# Ikaruga.net
KiCad netlist of a schematic drawn in EAGLE
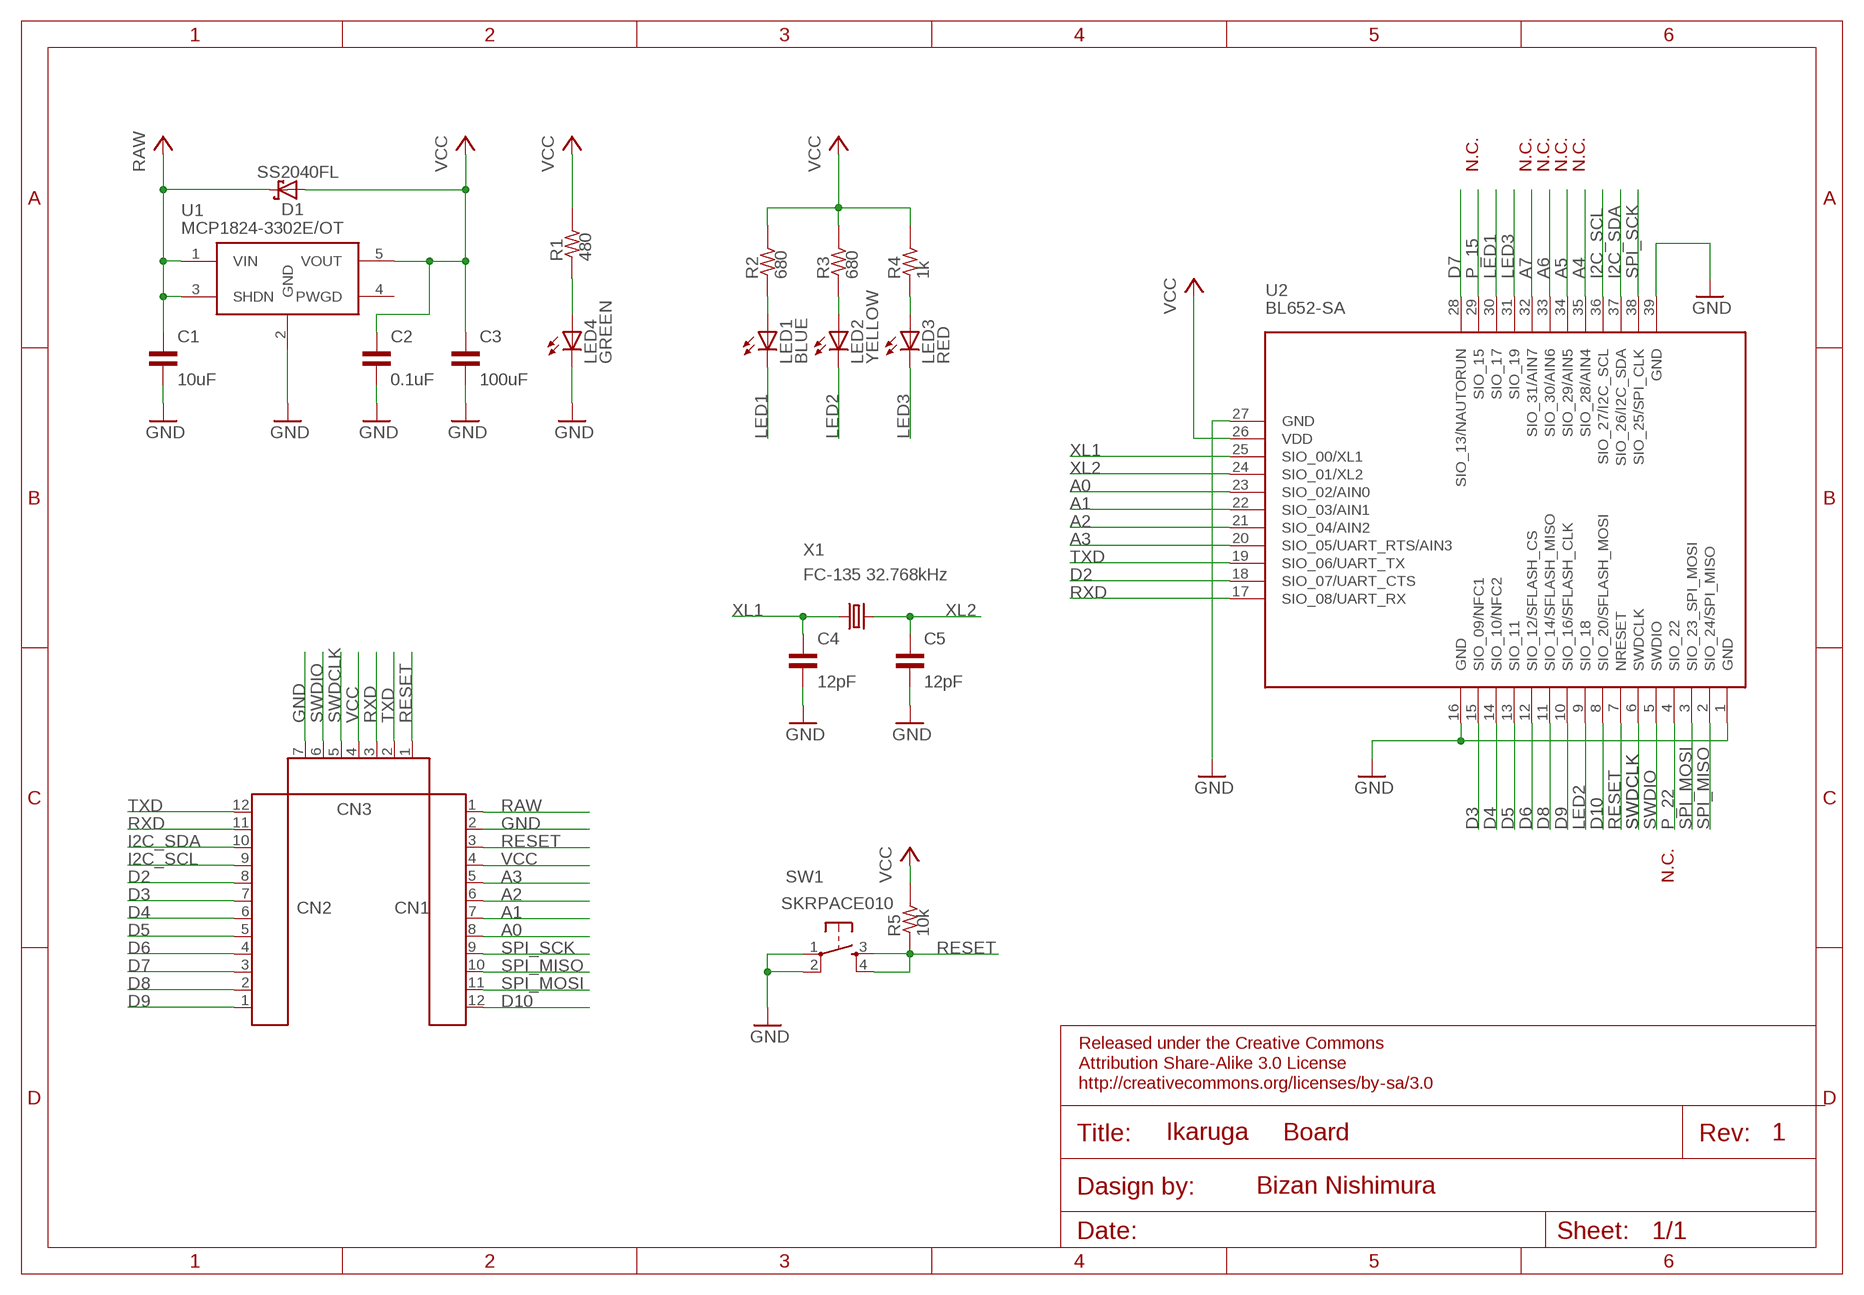
[diagram p0: schematic, sheet 1]

(export (version "E")
  (design (tool "Eeschema 10.0.6"))
  (components
    (comp (ref "C1")
      (value "10uF")
      (footprint "eagle-import:CP3216")
      (libsource (lib "eagle-import") (part "C-CP-3216"))
    )
    (comp (ref "C2")
      (value "0.1uF")
      (footprint "eagle-import:CP1608")
      (libsource (lib "eagle-import") (part "C-CP-1608"))
    )
    (comp (ref "C3")
      (value "100uF")
      (footprint "eagle-import:CP3216")
      (libsource (lib "eagle-import") (part "C-CP-3216"))
    )
    (comp (ref "C4")
      (value "12pF")
      (footprint "eagle-import:CP1608")
      (libsource (lib "eagle-import") (part "C-CP-1608"))
    )
    (comp (ref "C5")
      (value "12pF")
      (footprint "eagle-import:CP1608")
      (libsource (lib "eagle-import") (part "C-CP-1608"))
    )
    (comp (ref "CN1")
      (value "PINHD-1X12-NO-LINE")
      (footprint "eagle-import:1X12-NO-LINE")
      (libsource (lib "eagle-import") (part "PINHD-1X12-NO-LINE"))
    )
    (comp (ref "CN2")
      (value "PINHD-1X12-NO-LINE")
      (footprint "eagle-import:1X12-NO-LINE")
      (libsource (lib "eagle-import") (part "PINHD-1X12-NO-LINE"))
    )
    (comp (ref "CN3")
      (value "PINHD-1X7-NO-LINE")
      (footprint "eagle-import:1X07-NO-LINE")
      (libsource (lib "eagle-import") (part "PINHD-1X7-NO-LINE"))
    )
    (comp (ref "D1")
      (value "SS2040FL")
      (footprint "eagle-import:SOD123")
      (libsource (lib "eagle-import") (part "SCHOTTKY-DIODE-SOD123"))
    )
    (comp (ref "LED1")
      (value "BLUE")
      (footprint "eagle-import:LED1608")
      (libsource (lib "eagle-import") (part "LED1608"))
    )
    (comp (ref "LED2")
      (value "YELLOW")
      (footprint "eagle-import:LED1608")
      (libsource (lib "eagle-import") (part "LED1608"))
    )
    (comp (ref "LED3")
      (value "RED")
      (footprint "eagle-import:LED1608")
      (libsource (lib "eagle-import") (part "LED1608"))
    )
    (comp (ref "LED4")
      (value "GREEN")
      (footprint "eagle-import:LED1608")
      (libsource (lib "eagle-import") (part "LED1608"))
    )
    (comp (ref "R1")
      (value "480")
      (footprint "eagle-import:CP1608")
      (libsource (lib "eagle-import") (part "R-CP-1608"))
    )
    (comp (ref "R2")
      (value "680")
      (footprint "eagle-import:CP1608")
      (libsource (lib "eagle-import") (part "R-CP-1608"))
    )
    (comp (ref "R3")
      (value "680")
      (footprint "eagle-import:CP1608")
      (libsource (lib "eagle-import") (part "R-CP-1608"))
    )
    (comp (ref "R4")
      (value "1k")
      (footprint "eagle-import:CP1608")
      (libsource (lib "eagle-import") (part "R-CP-1608"))
    )
    (comp (ref "R5")
      (value "10k")
      (footprint "eagle-import:CP1608")
      (libsource (lib "eagle-import") (part "R-CP-1608"))
    )
    (comp (ref "SW1")
      (value "SKRPACE010")
      (footprint "eagle-import:SKRPACE010")
      (libsource (lib "eagle-import") (part "SKRPACE010"))
    )
    (comp (ref "U1")
      (value "MCP1824-3302E/OT")
      (footprint "eagle-import:SOT-23-5")
      (libsource (lib "eagle-import") (part "MCP1824-3302E/OT"))
    )
    (comp (ref "U2")
      (value "BL652-SA")
      (footprint "eagle-import:BL652-SA")
      (libsource (lib "eagle-import") (part "BL652-SA"))
    )
    (comp (ref "X1")
      (value "FC-135 32.768kHz")
      (footprint "eagle-import:FC-135")
      (libsource (lib "eagle-import") (part "FC-135"))
    )
  )
  (nets
    (net (code "1") (name "/A0") (class "Default")
      (node (ref "CN1") (pin "8") (pinfunction "8_8") (pintype "bidirectional"))
      (node (ref "U2") (pin "23") (pinfunction "SIO_02/AIN0_23") (pintype "bidirectional"))
    )
    (net (code "2") (name "/A1") (class "Default")
      (node (ref "CN1") (pin "7") (pinfunction "7_7") (pintype "bidirectional"))
      (node (ref "U2") (pin "22") (pinfunction "SIO_03/AIN1_22") (pintype "bidirectional"))
    )
    (net (code "3") (name "/A2") (class "Default")
      (node (ref "CN1") (pin "6") (pinfunction "6_6") (pintype "bidirectional"))
      (node (ref "U2") (pin "21") (pinfunction "SIO_04/AIN2_21") (pintype "bidirectional"))
    )
    (net (code "4") (name "/A3") (class "Default")
      (node (ref "CN1") (pin "5") (pinfunction "5_5") (pintype "bidirectional"))
      (node (ref "U2") (pin "20") (pinfunction "SIO_05/UART_RTS/AIN3_20") (pintype "bidirectional"))
    )
    (net (code "5") (name "/A4") (class "Default")
      (node (ref "U2") (pin "35") (pinfunction "SIO_28/AIN4_35") (pintype "bidirectional"))
    )
    (net (code "6") (name "/A5") (class "Default")
      (node (ref "U2") (pin "34") (pinfunction "SIO_29/AIN5_34") (pintype "bidirectional"))
    )
    (net (code "7") (name "/A6") (class "Default")
      (node (ref "U2") (pin "33") (pinfunction "SIO_30/AIN6_33") (pintype "bidirectional"))
    )
    (net (code "8") (name "/A7") (class "Default")
      (node (ref "U2") (pin "32") (pinfunction "SIO_31/AIN7_32") (pintype "bidirectional"))
    )
    (net (code "9") (name "/D2") (class "Default")
      (node (ref "CN2") (pin "8") (pinfunction "8_8") (pintype "bidirectional"))
      (node (ref "U2") (pin "18") (pinfunction "SIO_07/UART_CTS_18") (pintype "bidirectional"))
    )
    (net (code "10") (name "/D3") (class "Default")
      (node (ref "CN2") (pin "7") (pinfunction "7_7") (pintype "bidirectional"))
      (node (ref "U2") (pin "15") (pinfunction "SIO_09/NFC1_15") (pintype "bidirectional"))
    )
    (net (code "11") (name "/D4") (class "Default")
      (node (ref "CN2") (pin "6") (pinfunction "6_6") (pintype "bidirectional"))
      (node (ref "U2") (pin "14") (pinfunction "SIO_10/NFC2_14") (pintype "bidirectional"))
    )
    (net (code "12") (name "/D5") (class "Default")
      (node (ref "CN2") (pin "5") (pinfunction "5_5") (pintype "bidirectional"))
      (node (ref "U2") (pin "13") (pinfunction "SIO_11_13") (pintype "bidirectional"))
    )
    (net (code "13") (name "/D6") (class "Default")
      (node (ref "CN2") (pin "4") (pinfunction "4_4") (pintype "bidirectional"))
      (node (ref "U2") (pin "12") (pinfunction "SIO_12/SFLASH_CS_12") (pintype "bidirectional"))
    )
    (net (code "14") (name "/D7") (class "Default")
      (node (ref "CN2") (pin "3") (pinfunction "3_3") (pintype "bidirectional"))
      (node (ref "U2") (pin "28") (pinfunction "SIO_13/NAUTORUN_28") (pintype "bidirectional"))
    )
    (net (code "15") (name "/D8") (class "Default")
      (node (ref "CN2") (pin "2") (pinfunction "2_2") (pintype "bidirectional"))
      (node (ref "U2") (pin "11") (pinfunction "SIO_14/SFLASH_MISO_11") (pintype "bidirectional"))
    )
    (net (code "16") (name "/D9") (class "Default")
      (node (ref "CN2") (pin "1") (pinfunction "1_1") (pintype "bidirectional"))
      (node (ref "U2") (pin "10") (pinfunction "SIO_16/SFLASH_CLK_10") (pintype "bidirectional"))
    )
    (net (code "17") (name "/D10") (class "Default")
      (node (ref "CN1") (pin "12") (pinfunction "12_12") (pintype "bidirectional"))
      (node (ref "U2") (pin "8") (pinfunction "SIO_20/SFLASH_MOSI_8") (pintype "bidirectional"))
    )
    (net (code "18") (name "/I2C_SCL") (class "Default")
      (node (ref "CN2") (pin "9") (pinfunction "9_9") (pintype "bidirectional"))
      (node (ref "U2") (pin "36") (pinfunction "SIO_27/I2C_SCL_36") (pintype "bidirectional"))
    )
    (net (code "19") (name "/I2C_SDA") (class "Default")
      (node (ref "CN2") (pin "10") (pinfunction "10_10") (pintype "bidirectional"))
      (node (ref "U2") (pin "37") (pinfunction "SIO_26/I2C_SDA_37") (pintype "bidirectional"))
    )
    (net (code "20") (name "/LED1") (class "Default")
      (node (ref "LED1") (pin "C") (pinfunction "C_C") (pintype "passive"))
      (node (ref "U2") (pin "30") (pinfunction "SIO_17_30") (pintype "bidirectional"))
    )
    (net (code "21") (name "/LED2") (class "Default")
      (node (ref "LED2") (pin "C") (pinfunction "C_C") (pintype "passive"))
      (node (ref "U2") (pin "9") (pinfunction "SIO_18_9") (pintype "bidirectional"))
    )
    (net (code "22") (name "/LED3") (class "Default")
      (node (ref "LED3") (pin "C") (pinfunction "C_C") (pintype "passive"))
      (node (ref "U2") (pin "31") (pinfunction "SIO_19_31") (pintype "bidirectional"))
    )
    (net (code "23") (name "/P_15") (class "Default")
      (node (ref "U2") (pin "29") (pinfunction "SIO_15_29") (pintype "bidirectional"))
    )
    (net (code "24") (name "/P_22") (class "Default")
      (node (ref "U2") (pin "4") (pinfunction "SIO_22_4") (pintype "bidirectional"))
    )
    (net (code "25") (name "/RESET") (class "Default")
      (node (ref "CN1") (pin "3") (pinfunction "3_3") (pintype "bidirectional"))
      (node (ref "CN3") (pin "1") (pinfunction "1_1") (pintype "bidirectional"))
      (node (ref "R5") (pin "SMD1") (pinfunction "PIN1_SMD1") (pintype "passive"))
      (node (ref "SW1") (pin "3") (pinfunction "3_3") (pintype "passive"))
      (node (ref "SW1") (pin "4") (pinfunction "4_4") (pintype "passive"))
      (node (ref "U2") (pin "7") (pinfunction "NRESET_7") (pintype "bidirectional"))
    )
    (net (code "26") (name "/RXD") (class "Default")
      (node (ref "CN2") (pin "11") (pinfunction "11_11") (pintype "bidirectional"))
      (node (ref "CN3") (pin "3") (pinfunction "3_3") (pintype "bidirectional"))
      (node (ref "U2") (pin "17") (pinfunction "SIO_08/UART_RX_17") (pintype "bidirectional"))
    )
    (net (code "27") (name "/SPI_MISO") (class "Default")
      (node (ref "CN1") (pin "10") (pinfunction "10_10") (pintype "bidirectional"))
      (node (ref "U2") (pin "2") (pinfunction "SIO_24/SPI_MISO_2") (pintype "bidirectional"))
    )
    (net (code "28") (name "/SPI_MOSI") (class "Default")
      (node (ref "CN1") (pin "11") (pinfunction "11_11") (pintype "bidirectional"))
      (node (ref "U2") (pin "3") (pinfunction "SIO_23_SPI_MOSI_3") (pintype "bidirectional"))
    )
    (net (code "29") (name "/SPI_SCK") (class "Default")
      (node (ref "CN1") (pin "9") (pinfunction "9_9") (pintype "bidirectional"))
      (node (ref "U2") (pin "38") (pinfunction "SIO_25/SPI_CLK_38") (pintype "bidirectional"))
    )
    (net (code "30") (name "/SWDCLK") (class "Default")
      (node (ref "CN3") (pin "5") (pinfunction "5_5") (pintype "bidirectional"))
      (node (ref "U2") (pin "6") (pinfunction "SWDCLK_6") (pintype "bidirectional"))
    )
    (net (code "31") (name "/SWDIO") (class "Default")
      (node (ref "CN3") (pin "6") (pinfunction "6_6") (pintype "bidirectional"))
      (node (ref "U2") (pin "5") (pinfunction "SWDIO_5") (pintype "bidirectional"))
    )
    (net (code "32") (name "/TXD") (class "Default")
      (node (ref "CN2") (pin "12") (pinfunction "12_12") (pintype "bidirectional"))
      (node (ref "CN3") (pin "2") (pinfunction "2_2") (pintype "bidirectional"))
      (node (ref "U2") (pin "19") (pinfunction "SIO_06/UART_TX_19") (pintype "bidirectional"))
    )
    (net (code "33") (name "/XL1") (class "Default")
      (node (ref "C4") (pin "SMD1") (pinfunction "PIN1_SMD1") (pintype "passive"))
      (node (ref "U2") (pin "25") (pinfunction "SIO_00/XL1_25") (pintype "bidirectional"))
      (node (ref "X1") (pin "1") (pinfunction "1_1") (pintype "passive"))
    )
    (net (code "34") (name "/XL2") (class "Default")
      (node (ref "C5") (pin "SMD1") (pinfunction "PIN1_SMD1") (pintype "passive"))
      (node (ref "U2") (pin "24") (pinfunction "SIO_01/XL2_24") (pintype "bidirectional"))
      (node (ref "X1") (pin "2") (pinfunction "2_2") (pintype "passive"))
    )
    (net (code "35") (name "GND") (class "Default")
      (node (ref "C1") (pin "SMD2") (pinfunction "PIN2_SMD2") (pintype "passive"))
      (node (ref "C2") (pin "SMD2") (pinfunction "PIN2_SMD2") (pintype "passive"))
      (node (ref "C3") (pin "SMD2") (pinfunction "PIN2_SMD2") (pintype "passive"))
      (node (ref "C4") (pin "SMD2") (pinfunction "PIN2_SMD2") (pintype "passive"))
      (node (ref "C5") (pin "SMD2") (pinfunction "PIN2_SMD2") (pintype "passive"))
      (node (ref "CN1") (pin "2") (pinfunction "2_2") (pintype "bidirectional"))
      (node (ref "CN3") (pin "7") (pinfunction "7_7") (pintype "bidirectional"))
      (node (ref "LED4") (pin "C") (pinfunction "C_C") (pintype "passive"))
      (node (ref "SW1") (pin "1") (pinfunction "1_1") (pintype "passive"))
      (node (ref "SW1") (pin "2") (pinfunction "2_2") (pintype "passive"))
      (node (ref "U1") (pin "2") (pinfunction "GND_2") (pintype "bidirectional"))
      (node (ref "U2") (pin "1") (pinfunction "GND_1") (pintype "bidirectional"))
      (node (ref "U2") (pin "16") (pinfunction "GND_16") (pintype "bidirectional"))
      (node (ref "U2") (pin "27") (pinfunction "GND_27") (pintype "bidirectional"))
      (node (ref "U2") (pin "39") (pinfunction "GND_39") (pintype "bidirectional"))
    )
    (net (code "36") (name "Net-(R1-PIN1)") (class "Default")
      (node (ref "LED4") (pin "A") (pinfunction "A_A") (pintype "passive"))
      (node (ref "R1") (pin "SMD1") (pinfunction "PIN1_SMD1") (pintype "passive"))
    )
    (net (code "37") (name "Net-(R2-PIN1)") (class "Default")
      (node (ref "LED1") (pin "A") (pinfunction "A_A") (pintype "passive"))
      (node (ref "R2") (pin "SMD1") (pinfunction "PIN1_SMD1") (pintype "passive"))
    )
    (net (code "38") (name "Net-(R3-PIN1)") (class "Default")
      (node (ref "LED2") (pin "A") (pinfunction "A_A") (pintype "passive"))
      (node (ref "R3") (pin "SMD1") (pinfunction "PIN1_SMD1") (pintype "passive"))
    )
    (net (code "39") (name "Net-(R4-PIN1)") (class "Default")
      (node (ref "LED3") (pin "A") (pinfunction "A_A") (pintype "passive"))
      (node (ref "R4") (pin "SMD1") (pinfunction "PIN1_SMD1") (pintype "passive"))
    )
    (net (code "40") (name "RAW") (class "Default")
      (node (ref "C1") (pin "SMD1") (pinfunction "PIN1_SMD1") (pintype "passive"))
      (node (ref "CN1") (pin "1") (pinfunction "1_1") (pintype "bidirectional"))
      (node (ref "D1") (pin "C") (pinfunction "C_C") (pintype "passive"))
      (node (ref "U1") (pin "1") (pinfunction "VIN_1") (pintype "bidirectional"))
      (node (ref "U1") (pin "3") (pinfunction "SHDN_3") (pintype "bidirectional"))
    )
    (net (code "41") (name "VCC") (class "Default")
      (node (ref "C2") (pin "SMD1") (pinfunction "PIN1_SMD1") (pintype "passive"))
      (node (ref "C3") (pin "SMD1") (pinfunction "PIN1_SMD1") (pintype "passive"))
      (node (ref "CN1") (pin "4") (pinfunction "4_4") (pintype "bidirectional"))
      (node (ref "CN3") (pin "4") (pinfunction "4_4") (pintype "bidirectional"))
      (node (ref "D1") (pin "A") (pinfunction "A_A") (pintype "passive"))
      (node (ref "R1") (pin "SMD2") (pinfunction "PIN2_SMD2") (pintype "passive"))
      (node (ref "R2") (pin "SMD2") (pinfunction "PIN2_SMD2") (pintype "passive"))
      (node (ref "R3") (pin "SMD2") (pinfunction "PIN2_SMD2") (pintype "passive"))
      (node (ref "R4") (pin "SMD2") (pinfunction "PIN2_SMD2") (pintype "passive"))
      (node (ref "R5") (pin "SMD2") (pinfunction "PIN2_SMD2") (pintype "passive"))
      (node (ref "U1") (pin "5") (pinfunction "VOUT_5") (pintype "bidirectional"))
      (node (ref "U2") (pin "26") (pinfunction "VDD_26") (pintype "bidirectional"))
    )
    (net (code "42") (name "unconnected-(U1-PWGD-Pad4)") (class "Default")
      (node (ref "U1") (pin "4") (pinfunction "PWGD_4") (pintype "bidirectional"))
    )
  )
)
